# FTDI_ToolKit_FTDI_USB.net
KiCad netlist of a schematic drawn in Altium Designer
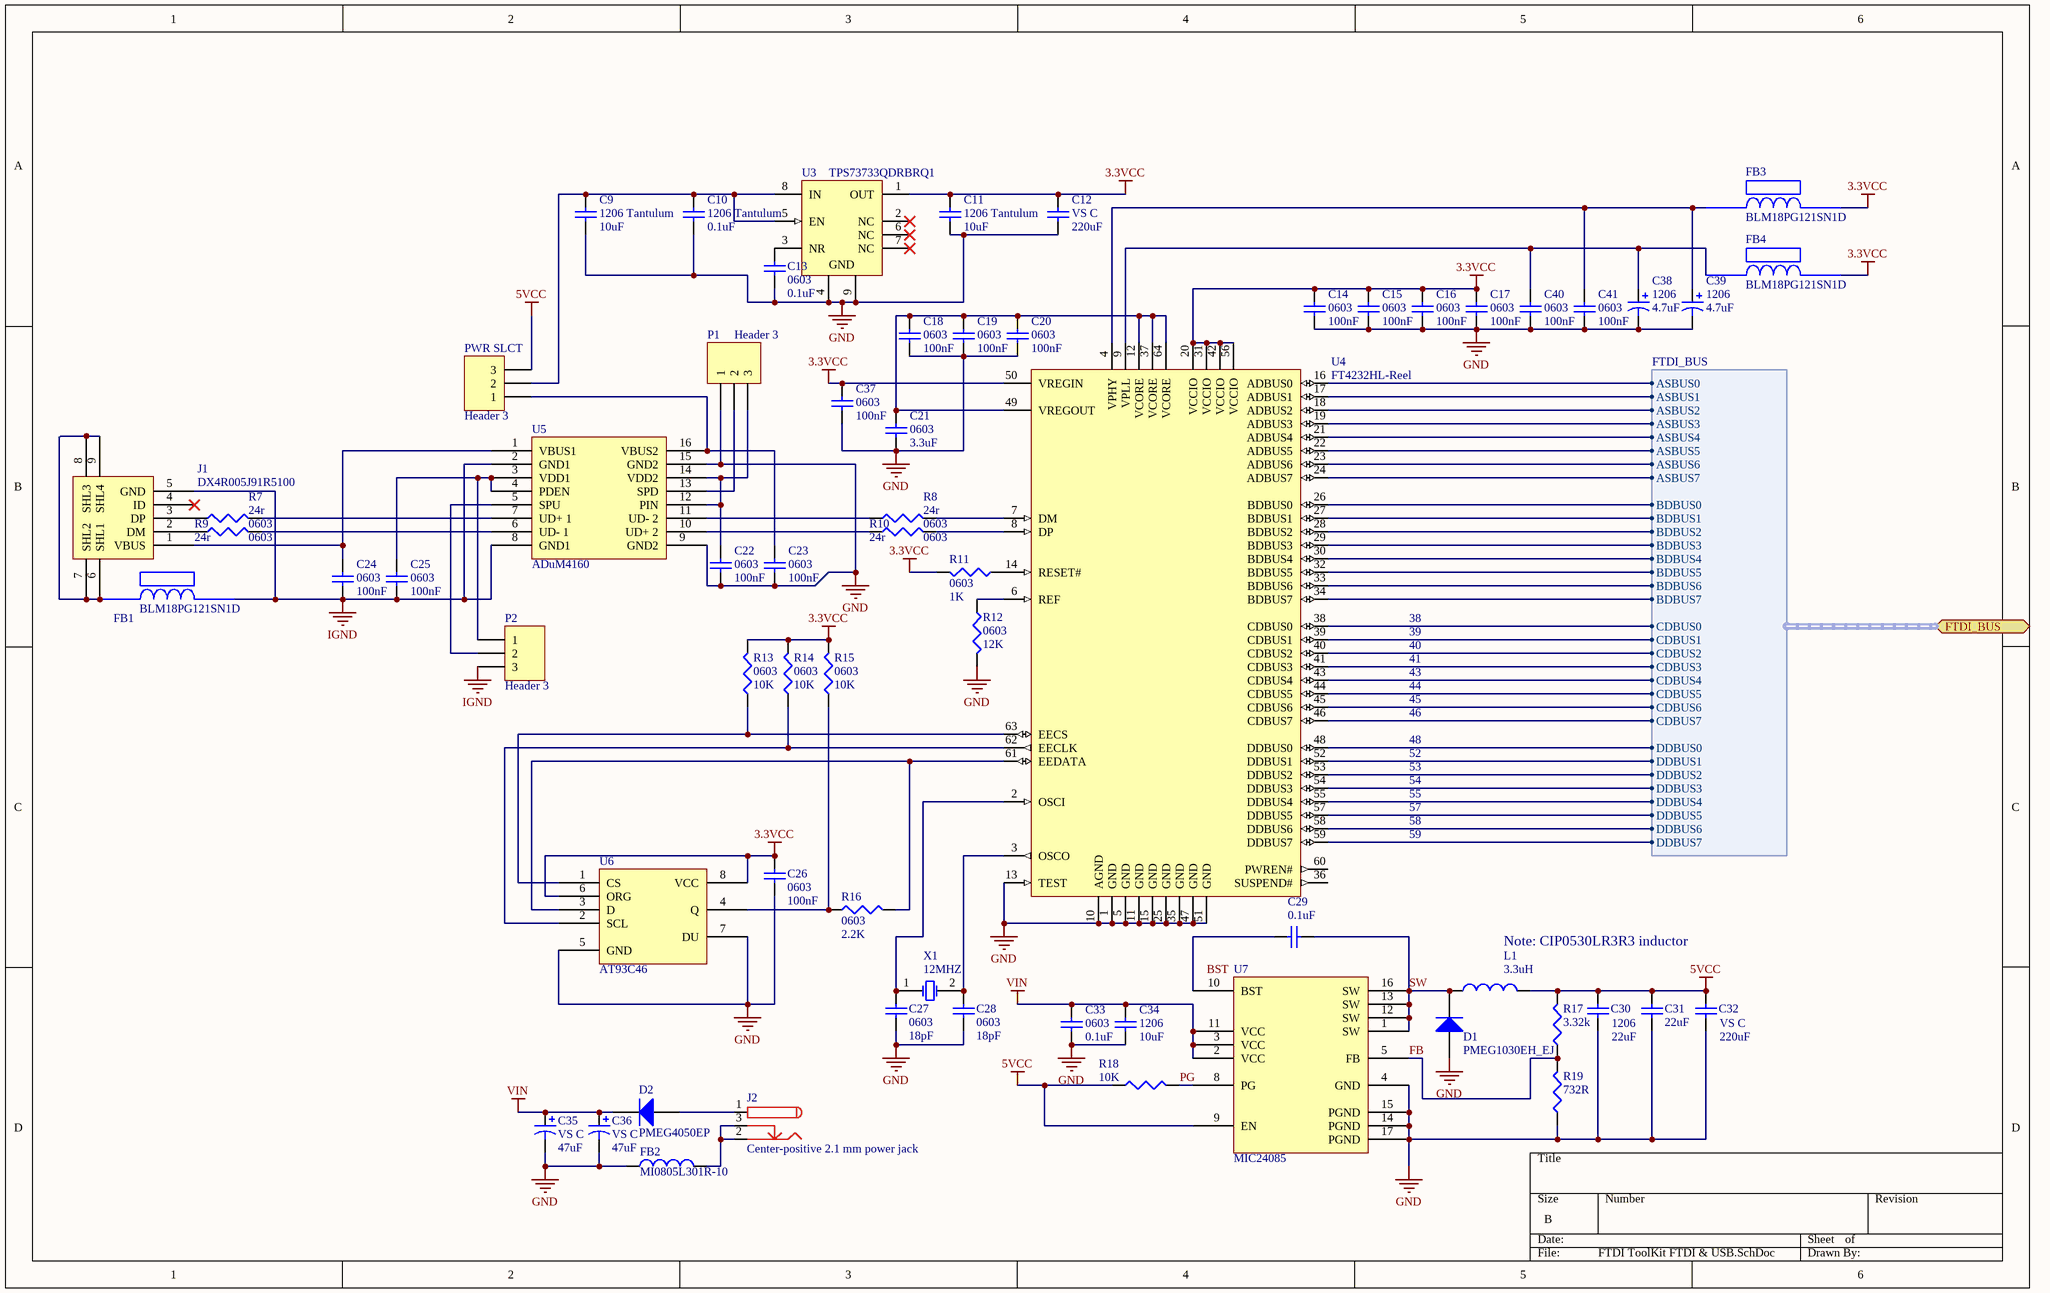
[diagram p0: FTDI ToolKit FTDI & USB.SchDoc]

(export (version "E")
  (design (tool "Eeschema 10.0.6"))
  (components
    (comp (ref "C9")
      (value "1206 Tantulum")
      (footprint "C1206")
      (description "Capacitor (Semiconductor SIM Model)")
      (fields (field (name "ALTIUM_VALUE") "10uF") (field (name "PUBLISHER") "Altium Limited"))
      (libsource (lib "Miscellaneous Devices") (part "Cap Semi"))
    )
    (comp (ref "C10")
      (value "1206 Tantulum")
      (footprint "C1206")
      (description "Capacitor (Semiconductor SIM Model)")
      (fields (field (name "ALTIUM_VALUE") "0.1uF") (field (name "PUBLISHER") "Altium Limited"))
      (libsource (lib "Miscellaneous Devices") (part "Cap Semi"))
    )
    (comp (ref "C11")
      (value "1206 Tantulum")
      (footprint "C1206")
      (description "Capacitor (Semiconductor SIM Model)")
      (fields (field (name "ALTIUM_VALUE") "10uF") (field (name "PUBLISHER") "Altium Limited"))
      (libsource (lib "Miscellaneous Devices") (part "Cap Semi"))
    )
    (comp (ref "C12")
      (value "VS C")
      (footprint "Panasonic VS C")
      (description "Capacitor (Semiconductor SIM Model)")
      (fields (field (name "ALTIUM_VALUE") "220uF") (field (name "PUBLISHER") "Altium Limited"))
      (libsource (lib "Miscellaneous Devices") (part "Cap Semi"))
    )
    (comp (ref "C13")
      (value "0603")
      (footprint "1608[0603]")
      (description "Capacitor (Semiconductor SIM Model)")
      (fields (field (name "ALTIUM_VALUE") "0.1uF") (field (name "PUBLISHER") "Altium Limited"))
      (libsource (lib "Miscellaneous Devices") (part "Cap Semi"))
    )
    (comp (ref "C14")
      (value "0603")
      (footprint "1608[0603]")
      (description "Capacitor (Semiconductor SIM Model)")
      (fields (field (name "ALTIUM_VALUE") "100nF") (field (name "PUBLISHER") "Altium Limited"))
      (libsource (lib "Miscellaneous Devices") (part "Cap Semi"))
    )
    (comp (ref "C15")
      (value "0603")
      (footprint "1608[0603]")
      (description "Capacitor (Semiconductor SIM Model)")
      (fields (field (name "ALTIUM_VALUE") "100nF") (field (name "PUBLISHER") "Altium Limited"))
      (libsource (lib "Miscellaneous Devices") (part "Cap Semi"))
    )
    (comp (ref "C16")
      (value "0603")
      (footprint "1608[0603]")
      (description "Capacitor (Semiconductor SIM Model)")
      (fields (field (name "ALTIUM_VALUE") "100nF") (field (name "PUBLISHER") "Altium Limited"))
      (libsource (lib "Miscellaneous Devices") (part "Cap Semi"))
    )
    (comp (ref "C17")
      (value "0603")
      (footprint "1608[0603]")
      (description "Capacitor (Semiconductor SIM Model)")
      (fields (field (name "ALTIUM_VALUE") "100nF") (field (name "PUBLISHER") "Altium Limited"))
      (libsource (lib "Miscellaneous Devices") (part "Cap Semi"))
    )
    (comp (ref "C18")
      (value "0603")
      (footprint "1608[0603]")
      (description "Capacitor (Semiconductor SIM Model)")
      (fields (field (name "ALTIUM_VALUE") "100nF") (field (name "PUBLISHER") "Altium Limited"))
      (libsource (lib "Miscellaneous Devices") (part "Cap Semi"))
    )
    (comp (ref "C19")
      (value "0603")
      (footprint "1608[0603]")
      (description "Capacitor (Semiconductor SIM Model)")
      (fields (field (name "ALTIUM_VALUE") "100nF") (field (name "PUBLISHER") "Altium Limited"))
      (libsource (lib "Miscellaneous Devices") (part "Cap Semi"))
    )
    (comp (ref "C20")
      (value "0603")
      (footprint "1608[0603]")
      (description "Capacitor (Semiconductor SIM Model)")
      (fields (field (name "ALTIUM_VALUE") "100nF") (field (name "PUBLISHER") "Altium Limited"))
      (libsource (lib "Miscellaneous Devices") (part "Cap Semi"))
    )
    (comp (ref "C21")
      (value "0603")
      (footprint "1608[0603]")
      (description "Capacitor (Semiconductor SIM Model)")
      (fields (field (name "ALTIUM_VALUE") "3.3uF") (field (name "PUBLISHER") "Altium Limited"))
      (libsource (lib "Miscellaneous Devices") (part "Cap Semi"))
    )
    (comp (ref "C22")
      (value "0603")
      (footprint "1608[0603]")
      (description "Capacitor (Semiconductor SIM Model)")
      (fields (field (name "ALTIUM_VALUE") "100nF") (field (name "PUBLISHER") "Altium Limited"))
      (libsource (lib "Miscellaneous Devices") (part "Cap Semi"))
    )
    (comp (ref "C23")
      (value "0603")
      (footprint "1608[0603]")
      (description "Capacitor (Semiconductor SIM Model)")
      (fields (field (name "ALTIUM_VALUE") "100nF") (field (name "PUBLISHER") "Altium Limited"))
      (libsource (lib "Miscellaneous Devices") (part "Cap Semi"))
    )
    (comp (ref "C24")
      (value "0603")
      (footprint "1608[0603]")
      (description "Capacitor (Semiconductor SIM Model)")
      (fields (field (name "ALTIUM_VALUE") "100nF") (field (name "PUBLISHER") "Altium Limited"))
      (libsource (lib "Miscellaneous Devices") (part "Cap Semi"))
    )
    (comp (ref "C25")
      (value "0603")
      (footprint "1608[0603]")
      (description "Capacitor (Semiconductor SIM Model)")
      (fields (field (name "ALTIUM_VALUE") "100nF") (field (name "PUBLISHER") "Altium Limited"))
      (libsource (lib "Miscellaneous Devices") (part "Cap Semi"))
    )
    (comp (ref "C26")
      (value "0603")
      (footprint "1608[0603]")
      (description "Capacitor (Semiconductor SIM Model)")
      (fields (field (name "ALTIUM_VALUE") "100nF") (field (name "PUBLISHER") "Altium Limited"))
      (libsource (lib "Miscellaneous Devices") (part "Cap Semi"))
    )
    (comp (ref "C27")
      (value "0603")
      (footprint "1608[0603]")
      (description "Capacitor (Semiconductor SIM Model)")
      (fields (field (name "ALTIUM_VALUE") "18pF") (field (name "PUBLISHER") "Altium Limited"))
      (libsource (lib "Miscellaneous Devices") (part "Cap Semi"))
    )
    (comp (ref "C28")
      (value "0603")
      (footprint "1608[0603]")
      (description "Capacitor (Semiconductor SIM Model)")
      (fields (field (name "ALTIUM_VALUE") "18pF") (field (name "PUBLISHER") "Altium Limited"))
      (libsource (lib "Miscellaneous Devices") (part "Cap Semi"))
    )
    (comp (ref "C29")
      (value "0.1uF")
      (footprint "1608[0603]")
      (description "Capacitor (Semiconductor SIM Model)")
      (fields (field (name "Comment") "Cap Semi") (field (name "PUBLISHER") "Altium Limited"))
      (libsource (lib "Miscellaneous Devices") (part "Cap Semi"))
    )
    (comp (ref "C30")
      (value "1206")
      (footprint "C1206")
      (description "Capacitor (Semiconductor SIM Model)")
      (fields (field (name "ALTIUM_VALUE") "22uF") (field (name "PUBLISHER") "Altium Limited"))
      (libsource (lib "Miscellaneous Devices") (part "Cap Semi"))
    )
    (comp (ref "C31")
      (value "22uF")
      (footprint "C1206")
      (description "Capacitor (Semiconductor SIM Model)")
      (fields (field (name "Comment") "Cap Semi") (field (name "PUBLISHER") "Altium Limited"))
      (libsource (lib "Miscellaneous Devices") (part "Cap Semi"))
    )
    (comp (ref "C32")
      (value "VS C")
      (footprint "Panasonic VS C")
      (description "Capacitor (Semiconductor SIM Model)")
      (fields (field (name "ALTIUM_VALUE") "220uF") (field (name "PUBLISHER") "Altium Limited"))
      (libsource (lib "Miscellaneous Devices") (part "Cap Semi"))
    )
    (comp (ref "C33")
      (value "0603")
      (footprint "1608[0603]")
      (description "Capacitor (Semiconductor SIM Model)")
      (fields (field (name "ALTIUM_VALUE") "0.1uF") (field (name "PUBLISHER") "Altium Limited"))
      (libsource (lib "Miscellaneous Devices") (part "Cap Semi"))
    )
    (comp (ref "C34")
      (value "1206")
      (footprint "C1206")
      (description "Capacitor (Semiconductor SIM Model)")
      (fields (field (name "ALTIUM_VALUE") "10uF") (field (name "PUBLISHER") "Altium Limited"))
      (libsource (lib "Miscellaneous Devices") (part "Cap Semi"))
    )
    (comp (ref "C35")
      (value "VS C")
      (footprint "Panasonic VS C")
      (description "Polarized Capacitor (Surface Mount)")
      (fields (field (name "ALTIUM_VALUE") "47uF") (field (name "PUBLISHER") "Altium Limited"))
      (libsource (lib "Miscellaneous Devices") (part "Cap Pol3"))
    )
    (comp (ref "C36")
      (value "VS C")
      (footprint "Panasonic VS C")
      (description "Polarized Capacitor (Surface Mount)")
      (fields (field (name "ALTIUM_VALUE") "47uF") (field (name "PUBLISHER") "Altium Limited"))
      (libsource (lib "Miscellaneous Devices") (part "Cap Pol3"))
    )
    (comp (ref "C37")
      (value "0603")
      (footprint "1608[0603]")
      (description "Capacitor (Semiconductor SIM Model)")
      (fields (field (name "ALTIUM_VALUE") "100nF") (field (name "PUBLISHER") "Altium Limited"))
      (libsource (lib "Miscellaneous Devices") (part "Cap Semi"))
    )
    (comp (ref "C38")
      (value "1206")
      (footprint "C1206POL")
      (description "Polarized Capacitor (Surface Mount)")
      (fields (field (name "ALTIUM_VALUE") "4.7uF") (field (name "PUBLISHER") "Altium Limited"))
      (libsource (lib "Miscellaneous Devices") (part "Cap Pol3"))
    )
    (comp (ref "C39")
      (value "1206")
      (footprint "C1206POL")
      (description "Polarized Capacitor (Surface Mount)")
      (fields (field (name "ALTIUM_VALUE") "4.7uF") (field (name "PUBLISHER") "Altium Limited"))
      (libsource (lib "Miscellaneous Devices") (part "Cap Pol3"))
    )
    (comp (ref "C40")
      (value "0603")
      (footprint "1608[0603]")
      (description "Capacitor (Semiconductor SIM Model)")
      (fields (field (name "ALTIUM_VALUE") "100nF") (field (name "PUBLISHER") "Altium Limited"))
      (libsource (lib "Miscellaneous Devices") (part "Cap Semi"))
    )
    (comp (ref "C41")
      (value "0603")
      (footprint "1608[0603]")
      (description "Capacitor (Semiconductor SIM Model)")
      (fields (field (name "ALTIUM_VALUE") "100nF") (field (name "PUBLISHER") "Altium Limited"))
      (libsource (lib "Miscellaneous Devices") (part "Cap Semi"))
    )
    (comp (ref "D1")
      (value "PMEG1030EH_EJ")
      (footprint "PMEG1030EH_EJ")
      (description "Default Diode")
      (fields (field (name "PUBLISHER") "Altium Limited"))
      (libsource (lib "") (part "Diode_1"))
    )
    (comp (ref "D2")
      (value "PMEG4050EP")
      (footprint "PMEG4050EP")
      (description "Default Diode")
      (fields (field (name "PUBLISHER") "Altium Limited"))
      (libsource (lib "Miscellaneous Devices") (part "Diode"))
    )
    (comp (ref "FB1")
      (value "BLM18PG121SN1D")
      (footprint "BLM18PG121SN1D")
      (libsource (lib "Adams Altium Library") (part "BLM18PG121SN1D"))
    )
    (comp (ref "FB2")
      (value "MI0805L301R-10")
      (footprint "SM 0805 - gap trimmed")
      (description "Inductor")
      (fields (field (name "PUBLISHER") "Altium Limited"))
      (libsource (lib "Miscellaneous Devices") (part "Inductor"))
    )
    (comp (ref "FB3")
      (value "BLM18PG121SN1D")
      (footprint "BLM18PG121SN1D")
      (libsource (lib "Adams Altium Library") (part "BLM18PG121SN1D"))
    )
    (comp (ref "FB4")
      (value "BLM18PG121SN1D")
      (footprint "BLM18PG121SN1D")
      (libsource (lib "Adams Altium Library") (part "BLM18PG121SN1D"))
    )
    (comp (ref "J1")
      (value "DX4R005J91R5100")
      (footprint "Micro USB Circular Holes Only")
      (description "Micro USB Jack B")
      (libsource (lib "Adams Altium Library") (part "Micro USB"))
    )
    (comp (ref "J2")
      (value "Center-positive 2.1 mm power jack")
      (footprint "PJ-102AH")
      (description "Power jack")
      (fields (field (name "PUBLISHER") "Altium Limited"))
      (libsource (lib "Adams Altium Library") (part "PWR2.5"))
    )
    (comp (ref "L1")
      (value "3.3uH")
      (footprint "CIP0530LR3R3")
      (description "Inductor")
      (fields (field (name "PUBLISHER") "Altium Limited"))
      (libsource (lib "Miscellaneous Devices") (part "Inductor"))
    )
    (comp (ref "P1")
      (value "Header 3")
      (footprint "HDR1X3")
      (description "Header, 3-Pin")
      (fields (field (name "PUBLISHER") "Altium Limited"))
      (libsource (lib "") (part "Header 3_2"))
    )
    (comp (ref "P2")
      (value "Header 3")
      (footprint "HDR1X3")
      (description "Header, 3-Pin")
      (fields (field (name "PUBLISHER") "Altium Limited"))
      (libsource (lib "") (part "Header 3_1"))
    )
    (comp (ref "PWR SLCT")
      (value "Header 3")
      (footprint "HDR1X3")
      (description "Header, 3-Pin")
      (fields (field (name "PUBLISHER") "Altium Limited"))
      (libsource (lib "Miscellaneous Connectors") (part "Header 3"))
    )
    (comp (ref "R7")
      (value "0603")
      (footprint "J1-0603")
      (description "Resistor")
      (fields (field (name "ALTIUM_VALUE") "24r") (field (name "PUBLISHER") "Altium Limited"))
      (libsource (lib "Miscellaneous Devices") (part "Res3"))
    )
    (comp (ref "R8")
      (value "0603")
      (footprint "J1-0603")
      (description "Resistor")
      (fields (field (name "ALTIUM_VALUE") "24r") (field (name "PUBLISHER") "Altium Limited"))
      (libsource (lib "Miscellaneous Devices") (part "Res3"))
    )
    (comp (ref "R9")
      (value "0603")
      (footprint "J1-0603")
      (description "Resistor")
      (fields (field (name "ALTIUM_VALUE") "24r") (field (name "PUBLISHER") "Altium Limited"))
      (libsource (lib "Miscellaneous Devices") (part "Res3"))
    )
    (comp (ref "R10")
      (value "0603")
      (footprint "J1-0603")
      (description "Resistor")
      (fields (field (name "ALTIUM_VALUE") "24r") (field (name "PUBLISHER") "Altium Limited"))
      (libsource (lib "Miscellaneous Devices") (part "Res3"))
    )
    (comp (ref "R11")
      (value "0603")
      (footprint "J1-0603")
      (description "Resistor")
      (fields (field (name "ALTIUM_VALUE") "1K") (field (name "PUBLISHER") "Altium Limited"))
      (libsource (lib "Miscellaneous Devices") (part "Res3"))
    )
    (comp (ref "R12")
      (value "0603")
      (footprint "J1-0603")
      (description "Resistor")
      (fields (field (name "ALTIUM_VALUE") "12K") (field (name "PUBLISHER") "Altium Limited"))
      (libsource (lib "Miscellaneous Devices") (part "Res3"))
    )
    (comp (ref "R13")
      (value "0603")
      (footprint "J1-0603")
      (description "Resistor")
      (fields (field (name "ALTIUM_VALUE") "10K") (field (name "PUBLISHER") "Altium Limited"))
      (libsource (lib "Miscellaneous Devices") (part "Res3"))
    )
    (comp (ref "R14")
      (value "0603")
      (footprint "J1-0603")
      (description "Resistor")
      (fields (field (name "ALTIUM_VALUE") "10K") (field (name "PUBLISHER") "Altium Limited"))
      (libsource (lib "Miscellaneous Devices") (part "Res3"))
    )
    (comp (ref "R15")
      (value "0603")
      (footprint "J1-0603")
      (description "Resistor")
      (fields (field (name "ALTIUM_VALUE") "10K") (field (name "PUBLISHER") "Altium Limited"))
      (libsource (lib "Miscellaneous Devices") (part "Res3"))
    )
    (comp (ref "R16")
      (value "0603")
      (footprint "J1-0603")
      (description "Resistor")
      (fields (field (name "ALTIUM_VALUE") "2.2K") (field (name "PUBLISHER") "Altium Limited"))
      (libsource (lib "Miscellaneous Devices") (part "Res3"))
    )
    (comp (ref "R17")
      (value "3.32k")
      (footprint "J1-0603")
      (description "Resistor")
      (fields (field (name "Comment") "Res3") (field (name "PUBLISHER") "Altium Limited"))
      (libsource (lib "Miscellaneous Devices") (part "Res3"))
    )
    (comp (ref "R18")
      (value "10K")
      (footprint "J1-0603")
      (description "Resistor")
      (fields (field (name "Comment") "Res3") (field (name "PUBLISHER") "Altium Limited"))
      (libsource (lib "Miscellaneous Devices") (part "Res3"))
    )
    (comp (ref "R19")
      (value "732R")
      (footprint "J1-0603")
      (description "Resistor")
      (fields (field (name "Comment") "Res3") (field (name "PUBLISHER") "Altium Limited"))
      (libsource (lib "Miscellaneous Devices") (part "Res3"))
    )
    (comp (ref "U3")
      (value "TPS73733QDRBRQ1")
      (footprint "TI-DRB8-1750X1500TP_V")
      (fields (field (name "MANUFACTURER") "Texas Instruments"))
      (libsource (lib "TI Power Management Linear Regulator Single Channel LDO (400-7500mA)") (part "TPS73733QDRBRQ1"))
    )
    (comp (ref "U4")
      (value "FT4232HL-Reel")
      (footprint "LQFP-64_N")
      (description "Quad High Speed USB To Multipurpose UART/MPSSE IC, 64-pin LQFP, Tape and Reel")
      (fields (field (name "MANUFACTURER") "FTDI"))
      (libsource (lib "FTDI FT Series") (part "FT4232HL-Reel"))
    )
    (comp (ref "U5")
      (value "ADuM4160")
      (footprint "ADuM4160")
      (description "USB Opto Isolator")
      (libsource (lib "AVR Board 4.0 Symbol Lib") (part "ADuM4160"))
    )
    (comp (ref "U6")
      (value "AT93C46")
      (footprint "SOIC127P600X175-8N")
      (libsource (lib "AVR Board 4.0 Symbol Lib") (part "AT93C46"))
    )
    (comp (ref "U7")
      (value "MIC24085")
      (footprint "MIC24085-AYML")
      (libsource (lib "Adams Altium Library") (part "MIC24085"))
    )
    (comp (ref "X1")
      (value "12MHZ")
      (footprint "445C35A12M00000")
      (description "Crystal Oscillator")
      (fields (field (name "PUBLISHER") "Altium Limited"))
      (libsource (lib "Miscellaneous Devices") (part "XTAL"))
    )
  )
  (nets
    (net (code "2") (name "/ASBUS0") (class "Default")
      (node (ref "U4") (pin "16") (pinfunction "ADBUS0_16") (pintype "bidirectional"))
    )
    (net (code "3") (name "/ASBUS1") (class "Default")
      (node (ref "U4") (pin "17") (pinfunction "ADBUS1_17") (pintype "bidirectional"))
    )
    (net (code "4") (name "/ASBUS2") (class "Default")
      (node (ref "U4") (pin "18") (pinfunction "ADBUS2_18") (pintype "bidirectional"))
    )
    (net (code "5") (name "/ASBUS3") (class "Default")
      (node (ref "U4") (pin "19") (pinfunction "ADBUS3_19") (pintype "bidirectional"))
    )
    (net (code "6") (name "/ASBUS4") (class "Default")
      (node (ref "U4") (pin "21") (pinfunction "ADBUS4_21") (pintype "bidirectional"))
    )
    (net (code "7") (name "/ASBUS5") (class "Default")
      (node (ref "U4") (pin "22") (pinfunction "ADBUS5_22") (pintype "bidirectional"))
    )
    (net (code "8") (name "/ASBUS6") (class "Default")
      (node (ref "U4") (pin "23") (pinfunction "ADBUS6_23") (pintype "bidirectional"))
    )
    (net (code "9") (name "/ASBUS7") (class "Default")
      (node (ref "U4") (pin "24") (pinfunction "ADBUS7_24") (pintype "bidirectional"))
    )
    (net (code "10") (name "/BDBUS0") (class "Default")
      (node (ref "U4") (pin "26") (pinfunction "BDBUS0_26") (pintype "bidirectional"))
    )
    (net (code "11") (name "/BDBUS1") (class "Default")
      (node (ref "U4") (pin "27") (pinfunction "BDBUS1_27") (pintype "bidirectional"))
    )
    (net (code "12") (name "/BDBUS2") (class "Default")
      (node (ref "U4") (pin "28") (pinfunction "BDBUS2_28") (pintype "bidirectional"))
    )
    (net (code "13") (name "/BDBUS3") (class "Default")
      (node (ref "U4") (pin "29") (pinfunction "BDBUS3_29") (pintype "bidirectional"))
    )
    (net (code "14") (name "/BDBUS4") (class "Default")
      (node (ref "U4") (pin "30") (pinfunction "BDBUS4_30") (pintype "bidirectional"))
    )
    (net (code "15") (name "/BDBUS5") (class "Default")
      (node (ref "U4") (pin "32") (pinfunction "BDBUS5_32") (pintype "bidirectional"))
    )
    (net (code "16") (name "/BDBUS6") (class "Default")
      (node (ref "U4") (pin "33") (pinfunction "BDBUS6_33") (pintype "bidirectional"))
    )
    (net (code "17") (name "/BDBUS7") (class "Default")
      (node (ref "U4") (pin "34") (pinfunction "BDBUS7_34") (pintype "bidirectional"))
    )
    (net (code "19") (name "/CDBUS0") (class "Default")
      (node (ref "U4") (pin "38") (pinfunction "CDBUS0_38") (pintype "bidirectional"))
    )
    (net (code "20") (name "/CDBUS1") (class "Default")
      (node (ref "U4") (pin "39") (pinfunction "CDBUS1_39") (pintype "bidirectional"))
    )
    (net (code "21") (name "/CDBUS2") (class "Default")
      (node (ref "U4") (pin "40") (pinfunction "CDBUS2_40") (pintype "bidirectional"))
    )
    (net (code "22") (name "/CDBUS3") (class "Default")
      (node (ref "U4") (pin "41") (pinfunction "CDBUS3_41") (pintype "bidirectional"))
    )
    (net (code "23") (name "/CDBUS4") (class "Default")
      (node (ref "U4") (pin "43") (pinfunction "CDBUS4_43") (pintype "bidirectional"))
    )
    (net (code "24") (name "/CDBUS5") (class "Default")
      (node (ref "U4") (pin "44") (pinfunction "CDBUS5_44") (pintype "bidirectional"))
    )
    (net (code "25") (name "/CDBUS6") (class "Default")
      (node (ref "U4") (pin "45") (pinfunction "CDBUS6_45") (pintype "bidirectional"))
    )
    (net (code "26") (name "/CDBUS7") (class "Default")
      (node (ref "U4") (pin "46") (pinfunction "CDBUS7_46") (pintype "bidirectional"))
    )
    (net (code "27") (name "/DDBUS0") (class "Default")
      (node (ref "U4") (pin "48") (pinfunction "DDBUS0_48") (pintype "bidirectional"))
    )
    (net (code "28") (name "/DDBUS1") (class "Default")
      (node (ref "U4") (pin "52") (pinfunction "DDBUS1_52") (pintype "bidirectional"))
    )
    (net (code "29") (name "/DDBUS2") (class "Default")
      (node (ref "U4") (pin "53") (pinfunction "DDBUS2_53") (pintype "bidirectional"))
    )
    (net (code "30") (name "/DDBUS3") (class "Default")
      (node (ref "U4") (pin "54") (pinfunction "DDBUS3_54") (pintype "bidirectional"))
    )
    (net (code "31") (name "/DDBUS4") (class "Default")
      (node (ref "U4") (pin "55") (pinfunction "DDBUS4_55") (pintype "bidirectional"))
    )
    (net (code "32") (name "/DDBUS5") (class "Default")
      (node (ref "U4") (pin "57") (pinfunction "DDBUS5_57") (pintype "bidirectional"))
    )
    (net (code "33") (name "/DDBUS6") (class "Default")
      (node (ref "U4") (pin "58") (pinfunction "DDBUS6_58") (pintype "bidirectional"))
    )
    (net (code "34") (name "/DDBUS7") (class "Default")
      (node (ref "U4") (pin "59") (pinfunction "DDBUS7_59") (pintype "bidirectional"))
    )
    (net (code "35") (name "/FB") (class "Default")
      (node (ref "R17") (pin "1") (pinfunction "1_1") (pintype "passive"))
      (node (ref "R19") (pin "2") (pinfunction "2_2") (pintype "passive"))
      (node (ref "U7") (pin "5") (pinfunction "FB_5") (pintype "passive"))
    )
    (net (code "36") (name "/PG") (class "Default")
      (node (ref "R18") (pin "2") (pinfunction "2_2") (pintype "passive"))
      (node (ref "U7") (pin "8") (pinfunction "PG_8") (pintype "passive"))
    )
    (net (code "37") (name "/SW") (class "Default")
      (node (ref "C29") (pin "1") (pinfunction "1_1") (pintype "passive"))
      (node (ref "D1") (pin "2") (pinfunction "K_2") (pintype "passive"))
      (node (ref "L1") (pin "1") (pinfunction "1_1") (pintype "passive"))
      (node (ref "U7") (pin "1") (pinfunction "SW_1") (pintype "passive"))
      (node (ref "U7") (pin "12") (pinfunction "SW_12") (pintype "passive"))
      (node (ref "U7") (pin "13") (pinfunction "SW_13") (pintype "passive"))
      (node (ref "U7") (pin "16") (pinfunction "SW_16") (pintype "passive"))
    )
    (net (code "39") (name "3.3VCC") (class "Default")
      (node (ref "C11") (pin "1") (pinfunction "1_1") (pintype "passive"))
      (node (ref "C12") (pin "1") (pinfunction "1_1") (pintype "passive"))
      (node (ref "C14") (pin "2") (pinfunction "2_2") (pintype "passive"))
      (node (ref "C15") (pin "2") (pinfunction "2_2") (pintype "passive"))
      (node (ref "C16") (pin "2") (pinfunction "2_2") (pintype "passive"))
      (node (ref "C17") (pin "2") (pinfunction "2_2") (pintype "passive"))
      (node (ref "C26") (pin "2") (pinfunction "2_2") (pintype "passive"))
      (node (ref "C37") (pin "2") (pinfunction "2_2") (pintype "passive"))
      (node (ref "FB3") (pin "2") (pinfunction "2_2") (pintype "passive"))
      (node (ref "FB4") (pin "2") (pinfunction "2_2") (pintype "passive"))
      (node (ref "R11") (pin "2") (pinfunction "2_2") (pintype "passive"))
      (node (ref "R13") (pin "2") (pinfunction "2_2") (pintype "passive"))
      (node (ref "R14") (pin "2") (pinfunction "2_2") (pintype "passive"))
      (node (ref "R15") (pin "2") (pinfunction "2_2") (pintype "passive"))
      (node (ref "U3") (pin "1") (pinfunction "OUT_1") (pintype "power_in"))
      (node (ref "U4") (pin "20") (pinfunction "VCCIO_20") (pintype "power_in"))
      (node (ref "U4") (pin "31") (pinfunction "VCCIO_31") (pintype "power_in"))
      (node (ref "U4") (pin "42") (pinfunction "VCCIO_42") (pintype "power_in"))
      (node (ref "U4") (pin "50") (pinfunction "VREGIN_50") (pintype "power_in"))
      (node (ref "U4") (pin "56") (pinfunction "VCCIO_56") (pintype "power_in"))
      (node (ref "U6") (pin "6") (pinfunction "ORG_6") (pintype "passive"))
      (node (ref "U6") (pin "8") (pinfunction "VCC_8") (pintype "passive"))
    )
    (net (code "40") (name "5VCC") (class "Default")
      (node (ref "C30") (pin "2") (pinfunction "2_2") (pintype "passive"))
      (node (ref "C31") (pin "1") (pinfunction "1_1") (pintype "passive"))
      (node (ref "C32") (pin "1") (pinfunction "1_1") (pintype "passive"))
      (node (ref "L1") (pin "2") (pinfunction "2_2") (pintype "passive"))
      (node (ref "PWR SLCT") (pin "3") (pinfunction "3_3") (pintype "passive"))
      (node (ref "R17") (pin "2") (pinfunction "2_2") (pintype "passive"))
      (node (ref "R18") (pin "1") (pinfunction "1_1") (pintype "passive"))
      (node (ref "U7") (pin "9") (pinfunction "EN_9") (pintype "passive"))
    )
    (net (code "41") (name "GND") (class "Default")
      (node (ref "C10") (pin "1") (pinfunction "1_1") (pintype "passive"))
      (node (ref "C11") (pin "2") (pinfunction "2_2") (pintype "passive"))
      (node (ref "C12") (pin "2") (pinfunction "2_2") (pintype "passive"))
      (node (ref "C13") (pin "1") (pinfunction "1_1") (pintype "passive"))
      (node (ref "C14") (pin "1") (pinfunction "1_1") (pintype "passive"))
      (node (ref "C15") (pin "1") (pinfunction "1_1") (pintype "passive"))
      (node (ref "C16") (pin "1") (pinfunction "1_1") (pintype "passive"))
      (node (ref "C17") (pin "1") (pinfunction "1_1") (pintype "passive"))
      (node (ref "C18") (pin "1") (pinfunction "1_1") (pintype "passive"))
      (node (ref "C19") (pin "1") (pinfunction "1_1") (pintype "passive"))
      (node (ref "C20") (pin "1") (pinfunction "1_1") (pintype "passive"))
      (node (ref "C21") (pin "1") (pinfunction "1_1") (pintype "passive"))
      (node (ref "C22") (pin "1") (pinfunction "1_1") (pintype "passive"))
      (node (ref "C23") (pin "1") (pinfunction "1_1") (pintype "passive"))
      (node (ref "C26") (pin "1") (pinfunction "1_1") (pintype "passive"))
      (node (ref "C27") (pin "1") (pinfunction "1_1") (pintype "passive"))
      (node (ref "C28") (pin "1") (pinfunction "1_1") (pintype "passive"))
      (node (ref "C30") (pin "1") (pinfunction "1_1") (pintype "passive"))
      (node (ref "C31") (pin "2") (pinfunction "2_2") (pintype "passive"))
      (node (ref "C32") (pin "2") (pinfunction "2_2") (pintype "passive"))
      (node (ref "C33") (pin "1") (pinfunction "1_1") (pintype "passive"))
      (node (ref "C34") (pin "1") (pinfunction "1_1") (pintype "passive"))
      (node (ref "C35") (pin "2") (pinfunction "2_2") (pintype "passive"))
      (node (ref "C36") (pin "2") (pinfunction "2_2") (pintype "passive"))
      (node (ref "C37") (pin "1") (pinfunction "1_1") (pintype "passive"))
      (node (ref "C38") (pin "2") (pinfunction "2_2") (pintype "passive"))
      (node (ref "C39") (pin "2") (pinfunction "2_2") (pintype "passive"))
      (node (ref "C40") (pin "1") (pinfunction "1_1") (pintype "passive"))
      (node (ref "C41") (pin "1") (pinfunction "1_1") (pintype "passive"))
      (node (ref "C9") (pin "2") (pinfunction "2_2") (pintype "passive"))
      (node (ref "D1") (pin "1") (pinfunction "A_1") (pintype "passive"))
      (node (ref "FB2") (pin "1") (pinfunction "1_1") (pintype "passive"))
      (node (ref "P1") (pin "1") (pinfunction "1_1") (pintype "passive"))
      (node (ref "R12") (pin "2") (pinfunction "2_2") (pintype "passive"))
      (node (ref "R19") (pin "1") (pinfunction "1_1") (pintype "passive"))
      (node (ref "U3") (pin "4") (pinfunction "GND_4") (pintype "power_in"))
      (node (ref "U3") (pin "9") (pinfunction "GND_9") (pintype "power_in"))
      (node (ref "U4") (pin "1") (pinfunction "GND_1") (pintype "power_in"))
      (node (ref "U4") (pin "10") (pinfunction "AGND_10") (pintype "power_in"))
      (node (ref "U4") (pin "11") (pinfunction "GND_11") (pintype "power_in"))
      (node (ref "U4") (pin "13") (pinfunction "TEST_13") (pintype "input"))
      (node (ref "U4") (pin "15") (pinfunction "GND_15") (pintype "power_in"))
      (node (ref "U4") (pin "25") (pinfunction "GND_25") (pintype "power_in"))
      (node (ref "U4") (pin "35") (pinfunction "GND_35") (pintype "power_in"))
      (node (ref "U4") (pin "47") (pinfunction "GND_47") (pintype "power_in"))
      (node (ref "U4") (pin "5") (pinfunction "GND_5") (pintype "power_in"))
      (node (ref "U4") (pin "51") (pinfunction "GND_51") (pintype "power_in"))
      (node (ref "U5") (pin "15") (pinfunction "GND2_15") (pintype "passive"))
      (node (ref "U5") (pin "9") (pinfunction "GND2_9") (pintype "passive"))
      (node (ref "U6") (pin "5") (pinfunction "GND_5") (pintype "passive"))
      (node (ref "U6") (pin "7") (pinfunction "DU_7") (pintype "passive"))
      (node (ref "U7") (pin "14") (pinfunction "PGND_14") (pintype "passive"))
      (node (ref "U7") (pin "15") (pinfunction "PGND_15") (pintype "passive"))
      (node (ref "U7") (pin "17") (pinfunction "PGND_17") (pintype "passive"))
      (node (ref "U7") (pin "4") (pinfunction "GND_4") (pintype "passive"))
    )
    (net (code "42") (name "IGND") (class "Default")
      (node (ref "C24") (pin "1") (pinfunction "1_1") (pintype "passive"))
      (node (ref "C25") (pin "1") (pinfunction "1_1") (pintype "passive"))
      (node (ref "FB1") (pin "2") (pinfunction "2_2") (pintype "passive"))
      (node (ref "J1") (pin "5") (pinfunction "GND_5") (pintype "passive"))
      (node (ref "P2") (pin "3") (pinfunction "3_3") (pintype "passive"))
      (node (ref "U5") (pin "2") (pinfunction "GND1_2") (pintype "passive"))
      (node (ref "U5") (pin "8") (pinfunction "GND1_8") (pintype "passive"))
    )
    (net (code "43") (name "Net-(D2-K)") (class "Default")
      (node (ref "D2") (pin "2") (pinfunction "K_2") (pintype "passive"))
      (node (ref "J2") (pin "1") (pinfunction "1_1") (pintype "power_in"))
    )
    (net (code "44") (name "Net-(FB2-Pad2)") (class "Default")
      (node (ref "FB2") (pin "2") (pinfunction "2_2") (pintype "passive"))
      (node (ref "J2") (pin "2") (pinfunction "2_2") (pintype "power_in"))
      (node (ref "J2") (pin "3") (pinfunction "3_3") (pintype "power_in"))
    )
    (net (code "45") (name "Net-(J1-DM)") (class "Default")
      (node (ref "J1") (pin "2") (pinfunction "DM_2") (pintype "passive"))
      (node (ref "R9") (pin "1") (pinfunction "1_1") (pintype "passive"))
    )
    (net (code "46") (name "Net-(J1-DP)") (class "Default")
      (node (ref "J1") (pin "3") (pinfunction "DP_3") (pintype "passive"))
      (node (ref "R7") (pin "1") (pinfunction "1_1") (pintype "passive"))
    )
    (net (code "47") (name "Net-(J1-SHL1)") (class "Default")
      (node (ref "FB1") (pin "1") (pinfunction "1_1") (pintype "passive"))
      (node (ref "J1") (pin "6") (pinfunction "SHL1_6") (pintype "passive"))
      (node (ref "J1") (pin "7") (pinfunction "SHL2_7") (pintype "passive"))
      (node (ref "J1") (pin "8") (pinfunction "SHL3_8") (pintype "passive"))
      (node (ref "J1") (pin "9") (pinfunction "SHL4_9") (pintype "passive"))
    )
    (net (code "48") (name "Net-(J1-VBUS)") (class "Default")
      (node (ref "C24") (pin "2") (pinfunction "2_2") (pintype "passive"))
      (node (ref "J1") (pin "1") (pinfunction "VBUS_1") (pintype "passive"))
      (node (ref "U5") (pin "1") (pinfunction "VBUS1_1") (pintype "passive"))
    )
    (net (code "49") (name "Net-(U3-EN)") (class "Default")
      (node (ref "C10") (pin "2") (pinfunction "2_2") (pintype "passive"))
      (node (ref "C9") (pin "1") (pinfunction "1_1") (pintype "passive"))
      (node (ref "PWR SLCT") (pin "2") (pinfunction "2_2") (pintype "passive"))
      (node (ref "U3") (pin "5") (pinfunction "EN_5") (pintype "input"))
      (node (ref "U3") (pin "8") (pinfunction "IN_8") (pintype "power_in"))
    )
    (net (code "50") (name "Net-(U3-NR)") (class "Default")
      (node (ref "C13") (pin "2") (pinfunction "2_2") (pintype "passive"))
      (node (ref "U3") (pin "3") (pinfunction "NR_3") (pintype "passive"))
    )
    (net (code "51") (name "Net-(U4-DM)") (class "Default")
      (node (ref "R8") (pin "2") (pinfunction "2_2") (pintype "passive"))
      (node (ref "U4") (pin "7") (pinfunction "DM_7") (pintype "input"))
    )
    (net (code "52") (name "Net-(U4-DP)") (class "Default")
      (node (ref "R10") (pin "2") (pinfunction "2_2") (pintype "passive"))
      (node (ref "U4") (pin "8") (pinfunction "DP_8") (pintype "input"))
    )
    (net (code "53") (name "Net-(U4-EECLK)") (class "Default")
      (node (ref "R14") (pin "1") (pinfunction "1_1") (pintype "passive"))
      (node (ref "U4") (pin "62") (pinfunction "EECLK_62") (pintype "output"))
      (node (ref "U6") (pin "2") (pinfunction "SCL_2") (pintype "passive"))
    )
    (net (code "54") (name "Net-(U4-EECS)") (class "Default")
      (node (ref "R13") (pin "1") (pinfunction "1_1") (pintype "passive"))
      (node (ref "U4") (pin "63") (pinfunction "EECS_63") (pintype "bidirectional"))
      (node (ref "U6") (pin "1") (pinfunction "CS_1") (pintype "passive"))
    )
    (net (code "55") (name "Net-(U4-EEDATA)") (class "Default")
      (node (ref "R16") (pin "2") (pinfunction "2_2") (pintype "passive"))
      (node (ref "U4") (pin "61") (pinfunction "EEDATA_61") (pintype "bidirectional"))
      (node (ref "U6") (pin "3") (pinfunction "D_3") (pintype "passive"))
    )
    (net (code "56") (name "Net-(U4-OSCI)") (class "Default")
      (node (ref "C27") (pin "2") (pinfunction "2_2") (pintype "passive"))
      (node (ref "U4") (pin "2") (pinfunction "OSCI_2") (pintype "input"))
      (node (ref "X1") (pin "1") (pinfunction "OSC1_1") (pintype "passive"))
    )
    (net (code "57") (name "Net-(U4-OSCO)") (class "Default")
      (node (ref "C28") (pin "2") (pinfunction "2_2") (pintype "passive"))
      (node (ref "U4") (pin "3") (pinfunction "OSCO_3") (pintype "output"))
      (node (ref "X1") (pin "2") (pinfunction "OSC2_2") (pintype "passive"))
    )
    (net (code "58") (name "Net-(U4-REF)") (class "Default")
      (node (ref "R12") (pin "1") (pinfunction "1_1") (pintype "passive"))
      (node (ref "U4") (pin "6") (pinfunction "REF_6") (pintype "input"))
    )
    (net (code "59") (name "Net-(U4-RESET#)") (class "Default")
      (node (ref "R11") (pin "1") (pinfunction "1_1") (pintype "passive"))
      (node (ref "U4") (pin "14") (pinfunction "RESET#_14") (pintype "input"))
    )
    (net (code "60") (name "Net-(U4-VPHY)") (class "Default")
      (node (ref "C39") (pin "1") (pinfunction "1_1") (pintype "passive"))
      (node (ref "C41") (pin "2") (pinfunction "2_2") (pintype "passive"))
      (node (ref "FB3") (pin "1") (pinfunction "1_1") (pintype "passive"))
      (node (ref "U4") (pin "4") (pinfunction "VPHY_4") (pintype "power_in"))
    )
    (net (code "61") (name "Net-(U4-VPLL)") (class "Default")
      (node (ref "C38") (pin "1") (pinfunction "1_1") (pintype "passive"))
      (node (ref "C40") (pin "2") (pinfunction "2_2") (pintype "passive"))
      (node (ref "FB4") (pin "1") (pinfunction "1_1") (pintype "passive"))
      (node (ref "U4") (pin "9") (pinfunction "VPLL_9") (pintype "power_in"))
    )
    (net (code "62") (name "Net-(U4-VREGOUT)") (class "Default")
      (node (ref "C18") (pin "2") (pinfunction "2_2") (pintype "passive"))
      (node (ref "C19") (pin "2") (pinfunction "2_2") (pintype "passive"))
      (node (ref "C20") (pin "2") (pinfunction "2_2") (pintype "passive"))
      (node (ref "C21") (pin "2") (pinfunction "2_2") (pintype "passive"))
      (node (ref "U4") (pin "12") (pinfunction "VCORE_12") (pintype "power_in"))
      (node (ref "U4") (pin "37") (pinfunction "VCORE_37") (pintype "power_in"))
      (node (ref "U4") (pin "49") (pinfunction "VREGOUT_49") (pintype "power_in"))
      (node (ref "U4") (pin "64") (pinfunction "VCORE_64") (pintype "power_in"))
    )
    (net (code "63") (name "Net-(U5-PDEN)") (class "Default")
      (node (ref "C25") (pin "2") (pinfunction "2_2") (pintype "passive"))
      (node (ref "P2") (pin "1") (pinfunction "1_1") (pintype "passive"))
      (node (ref "U5") (pin "3") (pinfunction "VDD1_3") (pintype "passive"))
      (node (ref "U5") (pin "4") (pinfunction "PDEN_4") (pintype "passive"))
    )
    (net (code "64") (name "Net-(U5-PIN)") (class "Default")
      (node (ref "C22") (pin "2") (pinfunction "2_2") (pintype "passive"))
      (node (ref "P1") (pin "3") (pinfunction "3_3") (pintype "passive"))
      (node (ref "U5") (pin "12") (pinfunction "PIN_12") (pintype "passive"))
      (node (ref "U5") (pin "14") (pinfunction "VDD2_14") (pintype "passive"))
    )
    (net (code "65") (name "Net-(U5-SPD)") (class "Default")
      (node (ref "P1") (pin "2") (pinfunction "2_2") (pintype "passive"))
      (node (ref "U5") (pin "13") (pinfunction "SPD_13") (pintype "passive"))
    )
    (net (code "66") (name "Net-(U5-SPU)") (class "Default")
      (node (ref "P2") (pin "2") (pinfunction "2_2") (pintype "passive"))
      (node (ref "U5") (pin "5") (pinfunction "SPU_5") (pintype "passive"))
    )
    (net (code "67") (name "Net-(U5-UD+_1)") (class "Default")
      (node (ref "R7") (pin "2") (pinfunction "2_2") (pintype "passive"))
      (node (ref "U5") (pin "7") (pinfunction "UD+_1_7") (pintype "passive"))
    )
    (net (code "68") (name "Net-(U5-UD+_2)") (class "Default")
      (node (ref "R10") (pin "1") (pinfunction "1_1") (pintype "passive"))
      (node (ref "U5") (pin "10") (pinfunction "UD+_2_10") (pintype "passive"))
    )
    (net (code "69") (name "Net-(U5-UD-_1)") (class "Default")
      (node (ref "R9") (pin "2") (pinfunction "2_2") (pintype "passive"))
      (node (ref "U5") (pin "6") (pinfunction "UD-_1_6") (pintype "passive"))
    )
    (net (code "70") (name "Net-(U5-UD-_2)") (class "Default")
      (node (ref "R8") (pin "1") (pinfunction "1_1") (pintype "passive"))
      (node (ref "U5") (pin "11") (pinfunction "UD-_2_11") (pintype "passive"))
    )
    (net (code "71") (name "Net-(U5-VBUS2)") (class "Default")
      (node (ref "C23") (pin "2") (pinfunction "2_2") (pintype "passive"))
      (node (ref "PWR SLCT") (pin "1") (pinfunction "1_1") (pintype "passive"))
      (node (ref "U5") (pin "16") (pinfunction "VBUS2_16") (pintype "passive"))
    )
    (net (code "72") (name "Net-(U6-Q)") (class "Default")
      (node (ref "R15") (pin "1") (pinfunction "1_1") (pintype "passive"))
      (node (ref "R16") (pin "1") (pinfunction "1_1") (pintype "passive"))
      (node (ref "U6") (pin "4") (pinfunction "Q_4") (pintype "passive"))
    )
    (net (code "73") (name "Net-(U7-BST)") (class "Default")
      (node (ref "C29") (pin "2") (pinfunction "2_2") (pintype "passive"))
      (node (ref "U7") (pin "10") (pinfunction "BST_10") (pintype "passive"))
    )
    (net (code "74") (name "VIN") (class "Default")
      (node (ref "C33") (pin "2") (pinfunction "2_2") (pintype "passive"))
      (node (ref "C34") (pin "2") (pinfunction "2_2") (pintype "passive"))
      (node (ref "C35") (pin "1") (pinfunction "1_1") (pintype "passive"))
      (node (ref "C36") (pin "1") (pinfunction "1_1") (pintype "passive"))
      (node (ref "D2") (pin "1") (pinfunction "A_1") (pintype "passive"))
      (node (ref "U7") (pin "11") (pinfunction "VCC_11") (pintype "passive"))
      (node (ref "U7") (pin "2") (pinfunction "VCC_2") (pintype "passive"))
      (node (ref "U7") (pin "3") (pinfunction "VCC_3") (pintype "passive"))
    )
    (net (code "75") (name "unconnected-(J1-ID-Pad4)") (class "Default")
      (node (ref "J1") (pin "4") (pinfunction "ID_4") (pintype "passive+no_connect"))
    )
    (net (code "76") (name "unconnected-(U3-NC-Pad2)") (class "Default")
      (node (ref "U3") (pin "2") (pinfunction "NC_2") (pintype "passive+no_connect"))
    )
    (net (code "77") (name "unconnected-(U3-NC-Pad6)") (class "Default")
      (node (ref "U3") (pin "6") (pinfunction "NC_6") (pintype "passive+no_connect"))
    )
    (net (code "78") (name "unconnected-(U3-NC-Pad7)") (class "Default")
      (node (ref "U3") (pin "7") (pinfunction "NC_7") (pintype "passive+no_connect"))
    )
    (net (code "79") (name "unconnected-(U4-PWREN#-Pad60)") (class "Default")
      (node (ref "U4") (pin "60") (pinfunction "PWREN#_60") (pintype "output"))
    )
    (net (code "80") (name "unconnected-(U4-SUSPEND#-Pad36)") (class "Default")
      (node (ref "U4") (pin "36") (pinfunction "SUSPEND#_36") (pintype "output"))
    )
    (net (code "81") (name "unconnected-(U7-NC-Pad6)") (class "Default")
      (node (ref "U7") (pin "6") (pinfunction "NC_6") (pintype "passive"))
    )
    (net (code "82") (name "unconnected-(U7-NC-Pad7)") (class "Default")
      (node (ref "U7") (pin "7") (pinfunction "NC_7") (pintype "passive"))
    )
  )
)
